# HeaderConnectorBoard.net
KiCad netlist of a schematic drawn in EAGLE
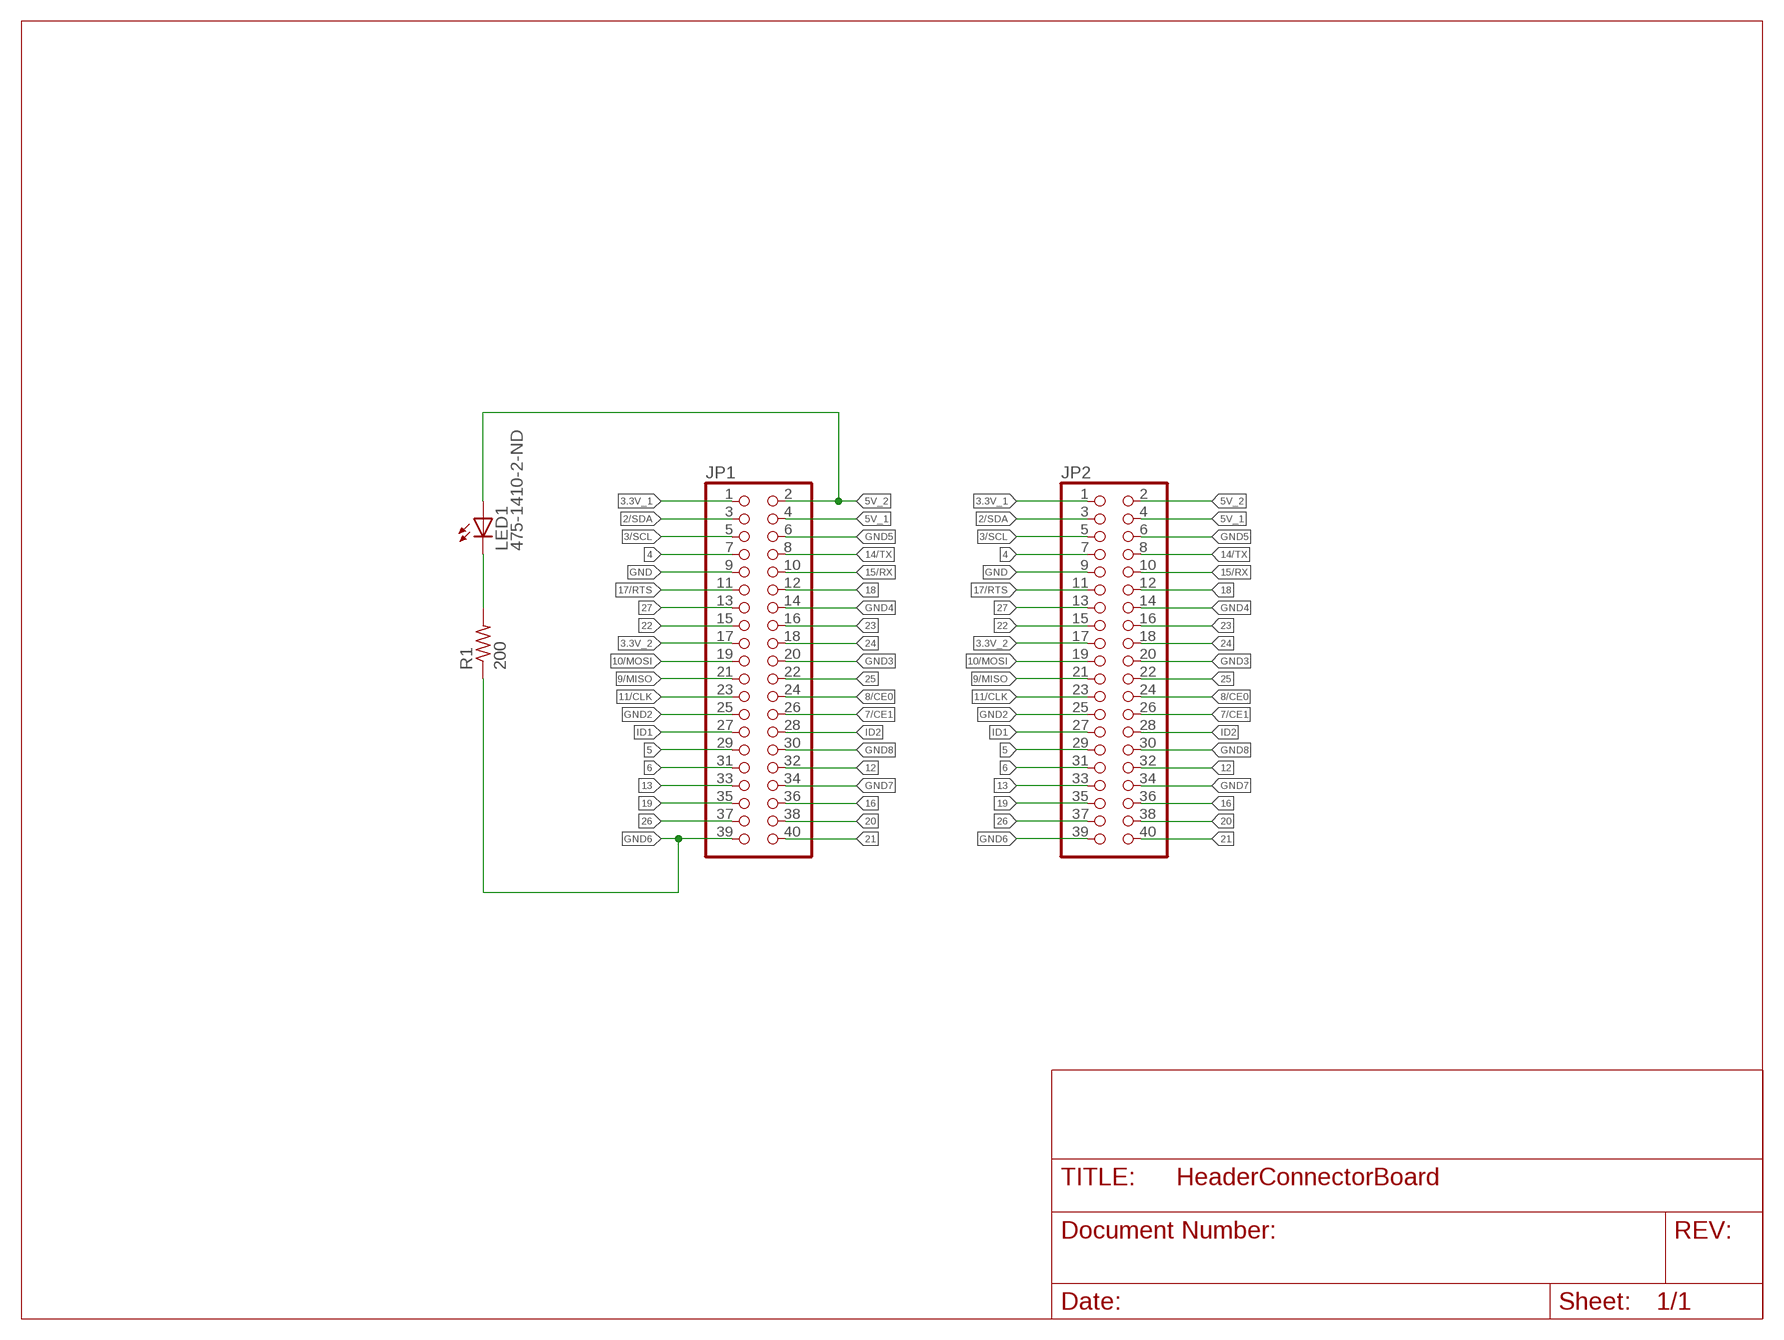
[diagram p0: schematic, sheet 1]

(export (version "E")
  (design (tool "Eeschema 10.0.6"))
  (components
    (comp (ref "JP1")
      (value "PINHD-2X20")
      (footprint "eagle-import:2X20")
      (libsource (lib "eagle-import") (part "PINHD-2X20"))
    )
    (comp (ref "JP2")
      (value "PINHD-2X20")
      (footprint "eagle-import:2X20")
      (libsource (lib "eagle-import") (part "PINHD-2X20"))
    )
    (comp (ref "LED1")
      (value "475-1410-2-ND")
      (footprint "eagle-import:CHIPLED_0805")
      (libsource (lib "eagle-import") (part "LEDCHIPLED_0805"))
    )
    (comp (ref "R1")
      (value "200")
      (footprint "eagle-import:R0805")
      (libsource (lib "eagle-import") (part "R-US_R0805"))
    )
  )
  (nets
    (net (code "1") (name "2{slash}SDA") (class "Default")
      (node (ref "JP1") (pin "3") (pinfunction "3_3") (pintype "passive"))
      (node (ref "JP2") (pin "3") (pinfunction "3_3") (pintype "passive"))
    )
    (net (code "2") (name "3.3V_1") (class "Default")
      (node (ref "JP1") (pin "1") (pinfunction "1_1") (pintype "passive"))
      (node (ref "JP2") (pin "1") (pinfunction "1_1") (pintype "passive"))
    )
    (net (code "3") (name "3.3V_2") (class "Default")
      (node (ref "JP1") (pin "17") (pinfunction "17_17") (pintype "passive"))
      (node (ref "JP2") (pin "17") (pinfunction "17_17") (pintype "passive"))
    )
    (net (code "4") (name "3{slash}SCL") (class "Default")
      (node (ref "JP1") (pin "5") (pinfunction "5_5") (pintype "passive"))
      (node (ref "JP2") (pin "5") (pinfunction "5_5") (pintype "passive"))
    )
    (net (code "5") (name "4") (class "Default")
      (node (ref "JP1") (pin "7") (pinfunction "7_7") (pintype "passive"))
      (node (ref "JP2") (pin "7") (pinfunction "7_7") (pintype "passive"))
    )
    (net (code "6") (name "5") (class "Default")
      (node (ref "JP1") (pin "29") (pinfunction "29_29") (pintype "passive"))
      (node (ref "JP2") (pin "29") (pinfunction "29_29") (pintype "passive"))
    )
    (net (code "7") (name "5V_1") (class "Default")
      (node (ref "JP1") (pin "4") (pinfunction "4_4") (pintype "passive"))
      (node (ref "JP2") (pin "4") (pinfunction "4_4") (pintype "passive"))
    )
    (net (code "8") (name "5V_2") (class "Default")
      (node (ref "JP1") (pin "2") (pinfunction "2_2") (pintype "passive"))
      (node (ref "JP2") (pin "2") (pinfunction "2_2") (pintype "passive"))
      (node (ref "LED1") (pin "A") (pinfunction "A_A") (pintype "passive"))
    )
    (net (code "9") (name "6") (class "Default")
      (node (ref "JP1") (pin "31") (pinfunction "31_31") (pintype "passive"))
      (node (ref "JP2") (pin "31") (pinfunction "31_31") (pintype "passive"))
    )
    (net (code "10") (name "7{slash}CE1") (class "Default")
      (node (ref "JP1") (pin "26") (pinfunction "26_26") (pintype "passive"))
      (node (ref "JP2") (pin "26") (pinfunction "26_26") (pintype "passive"))
    )
    (net (code "11") (name "8{slash}CE0") (class "Default")
      (node (ref "JP1") (pin "24") (pinfunction "24_24") (pintype "passive"))
      (node (ref "JP2") (pin "24") (pinfunction "24_24") (pintype "passive"))
    )
    (net (code "12") (name "9{slash}MISO") (class "Default")
      (node (ref "JP1") (pin "21") (pinfunction "21_21") (pintype "passive"))
      (node (ref "JP2") (pin "21") (pinfunction "21_21") (pintype "passive"))
    )
    (net (code "13") (name "10{slash}MOSI") (class "Default")
      (node (ref "JP1") (pin "19") (pinfunction "19_19") (pintype "passive"))
      (node (ref "JP2") (pin "19") (pinfunction "19_19") (pintype "passive"))
    )
    (net (code "14") (name "11{slash}CLK") (class "Default")
      (node (ref "JP1") (pin "23") (pinfunction "23_23") (pintype "passive"))
      (node (ref "JP2") (pin "23") (pinfunction "23_23") (pintype "passive"))
    )
    (net (code "15") (name "12") (class "Default")
      (node (ref "JP1") (pin "32") (pinfunction "32_32") (pintype "passive"))
      (node (ref "JP2") (pin "32") (pinfunction "32_32") (pintype "passive"))
    )
    (net (code "16") (name "13") (class "Default")
      (node (ref "JP1") (pin "33") (pinfunction "33_33") (pintype "passive"))
      (node (ref "JP2") (pin "33") (pinfunction "33_33") (pintype "passive"))
    )
    (net (code "17") (name "14{slash}TX") (class "Default")
      (node (ref "JP1") (pin "8") (pinfunction "8_8") (pintype "passive"))
      (node (ref "JP2") (pin "8") (pinfunction "8_8") (pintype "passive"))
    )
    (net (code "18") (name "15{slash}RX") (class "Default")
      (node (ref "JP1") (pin "10") (pinfunction "10_10") (pintype "passive"))
      (node (ref "JP2") (pin "10") (pinfunction "10_10") (pintype "passive"))
    )
    (net (code "19") (name "16") (class "Default")
      (node (ref "JP1") (pin "36") (pinfunction "36_36") (pintype "passive"))
      (node (ref "JP2") (pin "36") (pinfunction "36_36") (pintype "passive"))
    )
    (net (code "20") (name "17{slash}RTS") (class "Default")
      (node (ref "JP1") (pin "11") (pinfunction "11_11") (pintype "passive"))
      (node (ref "JP2") (pin "11") (pinfunction "11_11") (pintype "passive"))
    )
    (net (code "21") (name "18") (class "Default")
      (node (ref "JP1") (pin "12") (pinfunction "12_12") (pintype "passive"))
      (node (ref "JP2") (pin "12") (pinfunction "12_12") (pintype "passive"))
    )
    (net (code "22") (name "19") (class "Default")
      (node (ref "JP1") (pin "35") (pinfunction "35_35") (pintype "passive"))
      (node (ref "JP2") (pin "35") (pinfunction "35_35") (pintype "passive"))
    )
    (net (code "23") (name "20") (class "Default")
      (node (ref "JP1") (pin "38") (pinfunction "38_38") (pintype "passive"))
      (node (ref "JP2") (pin "38") (pinfunction "38_38") (pintype "passive"))
    )
    (net (code "24") (name "21") (class "Default")
      (node (ref "JP1") (pin "40") (pinfunction "40_40") (pintype "passive"))
      (node (ref "JP2") (pin "40") (pinfunction "40_40") (pintype "passive"))
    )
    (net (code "25") (name "22") (class "Default")
      (node (ref "JP1") (pin "15") (pinfunction "15_15") (pintype "passive"))
      (node (ref "JP2") (pin "15") (pinfunction "15_15") (pintype "passive"))
    )
    (net (code "26") (name "23") (class "Default")
      (node (ref "JP1") (pin "16") (pinfunction "16_16") (pintype "passive"))
      (node (ref "JP2") (pin "16") (pinfunction "16_16") (pintype "passive"))
    )
    (net (code "27") (name "24") (class "Default")
      (node (ref "JP1") (pin "18") (pinfunction "18_18") (pintype "passive"))
      (node (ref "JP2") (pin "18") (pinfunction "18_18") (pintype "passive"))
    )
    (net (code "28") (name "25") (class "Default")
      (node (ref "JP1") (pin "22") (pinfunction "22_22") (pintype "passive"))
      (node (ref "JP2") (pin "22") (pinfunction "22_22") (pintype "passive"))
    )
    (net (code "29") (name "26") (class "Default")
      (node (ref "JP1") (pin "37") (pinfunction "37_37") (pintype "passive"))
      (node (ref "JP2") (pin "37") (pinfunction "37_37") (pintype "passive"))
    )
    (net (code "30") (name "27") (class "Default")
      (node (ref "JP1") (pin "13") (pinfunction "13_13") (pintype "passive"))
      (node (ref "JP2") (pin "13") (pinfunction "13_13") (pintype "passive"))
    )
    (net (code "31") (name "GND") (class "Default")
      (node (ref "JP1") (pin "9") (pinfunction "9_9") (pintype "passive"))
      (node (ref "JP2") (pin "9") (pinfunction "9_9") (pintype "passive"))
    )
    (net (code "32") (name "GND2") (class "Default")
      (node (ref "JP1") (pin "25") (pinfunction "25_25") (pintype "passive"))
      (node (ref "JP2") (pin "25") (pinfunction "25_25") (pintype "passive"))
    )
    (net (code "33") (name "GND3") (class "Default")
      (node (ref "JP1") (pin "20") (pinfunction "20_20") (pintype "passive"))
      (node (ref "JP2") (pin "20") (pinfunction "20_20") (pintype "passive"))
    )
    (net (code "34") (name "GND4") (class "Default")
      (node (ref "JP1") (pin "14") (pinfunction "14_14") (pintype "passive"))
      (node (ref "JP2") (pin "14") (pinfunction "14_14") (pintype "passive"))
    )
    (net (code "35") (name "GND5") (class "Default")
      (node (ref "JP1") (pin "6") (pinfunction "6_6") (pintype "passive"))
      (node (ref "JP2") (pin "6") (pinfunction "6_6") (pintype "passive"))
    )
    (net (code "36") (name "GND6") (class "Default")
      (node (ref "JP1") (pin "39") (pinfunction "39_39") (pintype "passive"))
      (node (ref "JP2") (pin "39") (pinfunction "39_39") (pintype "passive"))
      (node (ref "R1") (pin "1") (pinfunction "1_1") (pintype "passive"))
    )
    (net (code "37") (name "GND7") (class "Default")
      (node (ref "JP1") (pin "34") (pinfunction "34_34") (pintype "passive"))
      (node (ref "JP2") (pin "34") (pinfunction "34_34") (pintype "passive"))
    )
    (net (code "38") (name "GND8") (class "Default")
      (node (ref "JP1") (pin "30") (pinfunction "30_30") (pintype "passive"))
      (node (ref "JP2") (pin "30") (pinfunction "30_30") (pintype "passive"))
    )
    (net (code "39") (name "ID1") (class "Default")
      (node (ref "JP1") (pin "27") (pinfunction "27_27") (pintype "passive"))
      (node (ref "JP2") (pin "27") (pinfunction "27_27") (pintype "passive"))
    )
    (net (code "40") (name "ID2") (class "Default")
      (node (ref "JP1") (pin "28") (pinfunction "28_28") (pintype "passive"))
      (node (ref "JP2") (pin "28") (pinfunction "28_28") (pintype "passive"))
    )
    (net (code "41") (name "Net-(LED1-PadC)") (class "Default")
      (node (ref "LED1") (pin "C") (pinfunction "C_C") (pintype "passive"))
      (node (ref "R1") (pin "2") (pinfunction "2_2") (pintype "passive"))
    )
  )
)
